# ESP_Bare_v2.net
KiCad netlist of a schematic drawn in EAGLE
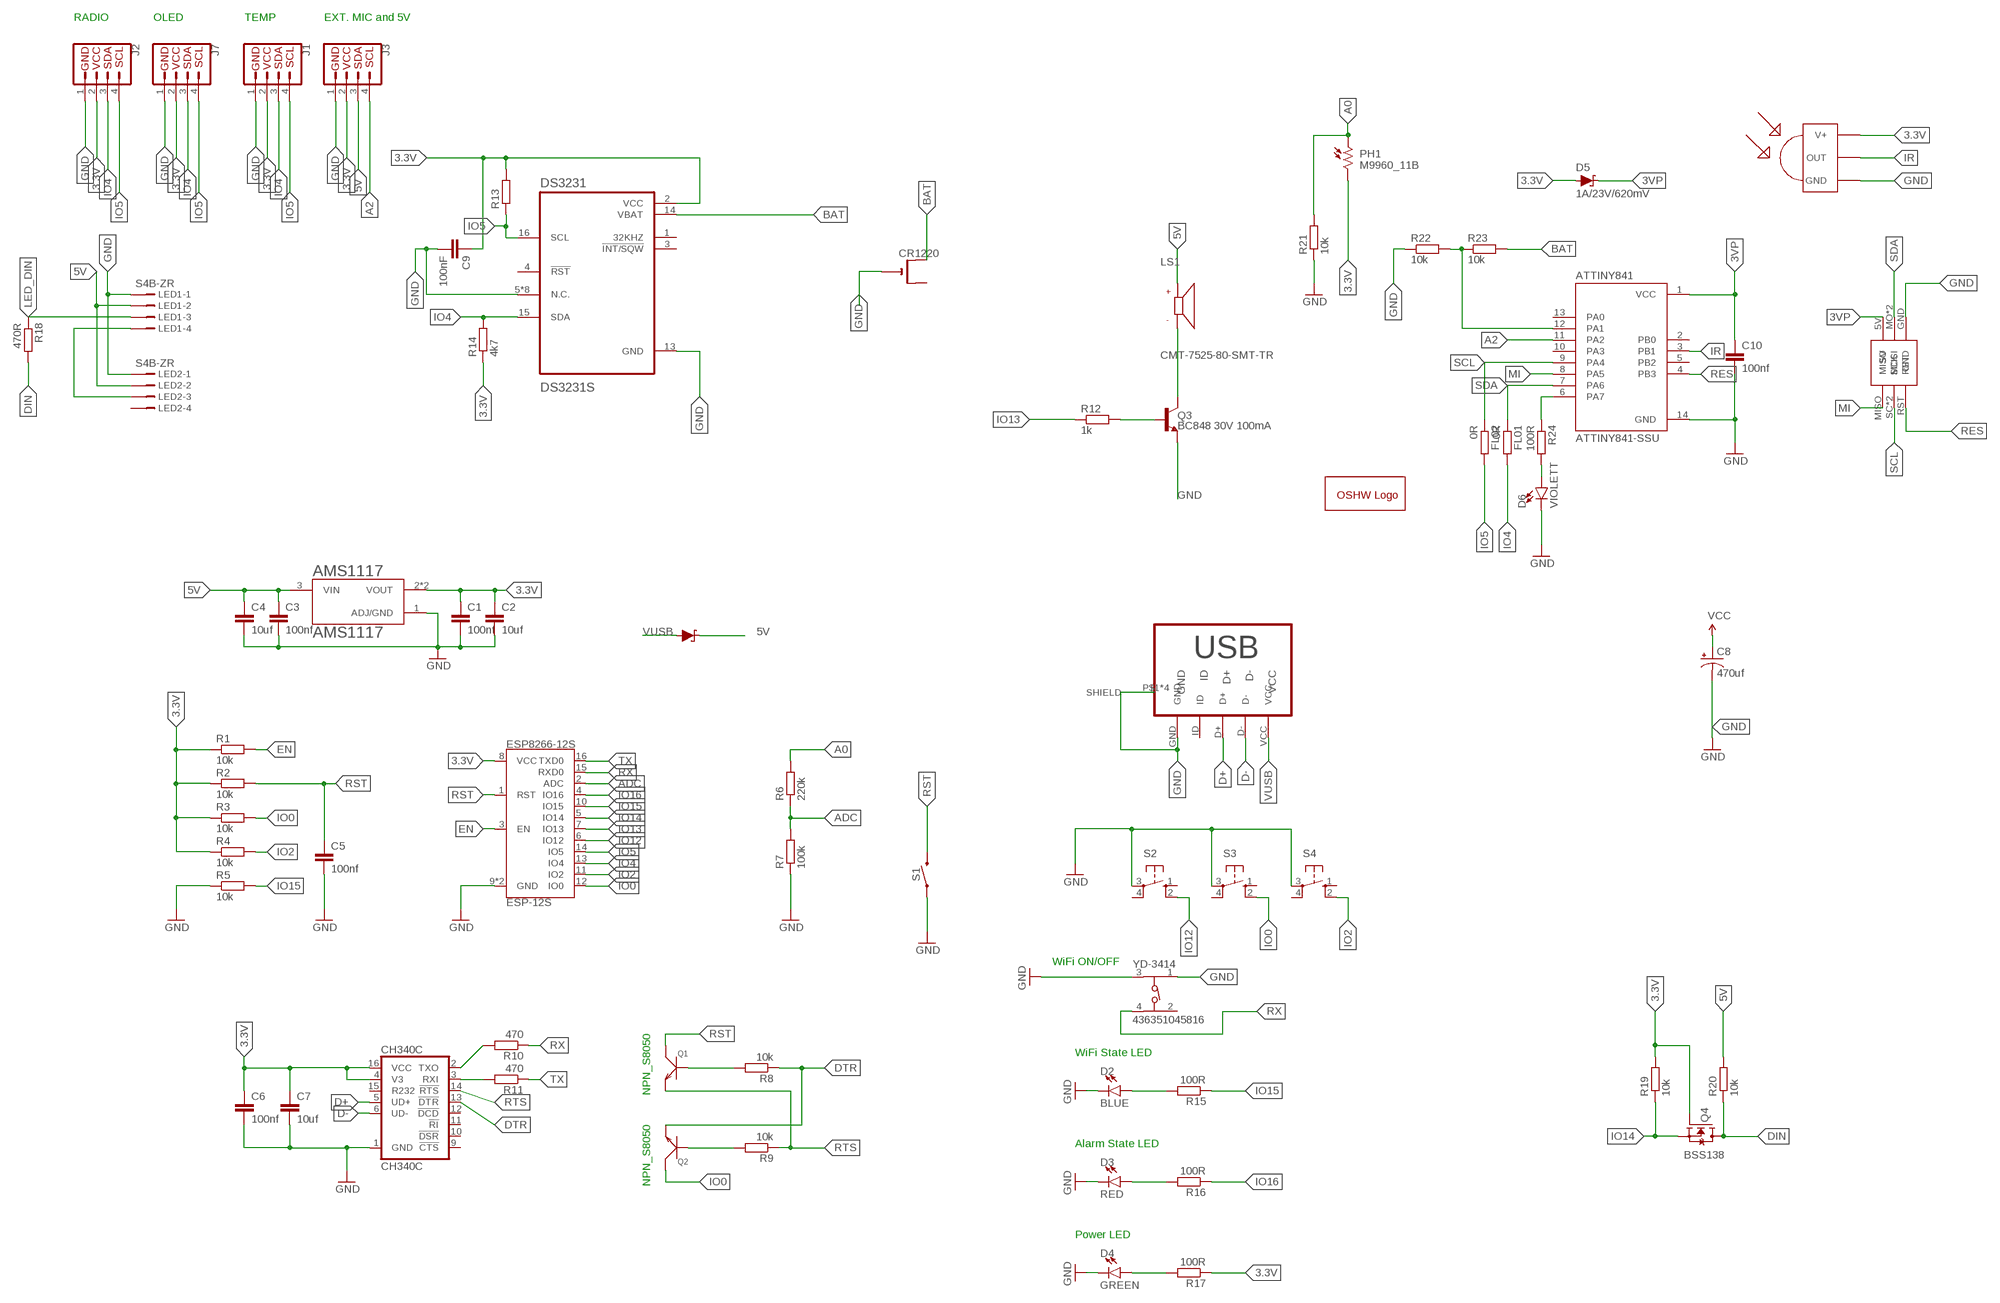
[diagram p0: schematic, sheet 1]

(export (version "E")
  (design (tool "Eeschema 10.0.6"))
  (components
    (comp (ref "AMS1117")
      (value "AMS1117")
      (footprint "eagle-import:SOT229P700X180-4N")
      (fields (field (name "MF") "Advanced Monolithic Systems"))
      (libsource (lib "eagle-import") (part "AMS1117"))
    )
    (comp (ref "ATTINY841")
      (value "ATTINY841-SSU")
      (footprint "eagle-import:SOIC127P599X175-14N")
      (fields (field (name "MF") "Microchip"))
      (libsource (lib "eagle-import") (part "ATTINY841-SSU"))
    )
    (comp (ref "C1")
      (value "100nf")
      (footprint "eagle-import:C0603")
      (libsource (lib "eagle-import") (part "C-EUC0603"))
    )
    (comp (ref "C2")
      (value "10uf")
      (footprint "eagle-import:C0805")
      (libsource (lib "eagle-import") (part "C-EUC0805"))
    )
    (comp (ref "C3")
      (value "100nf")
      (footprint "eagle-import:C0603")
      (libsource (lib "eagle-import") (part "C-EUC0603"))
    )
    (comp (ref "C4")
      (value "10uf")
      (footprint "eagle-import:C0805")
      (libsource (lib "eagle-import") (part "C-EUC0805"))
    )
    (comp (ref "C5")
      (value "100nf")
      (footprint "eagle-import:C0603")
      (libsource (lib "eagle-import") (part "C-EUC0603"))
    )
    (comp (ref "C6")
      (value "100nf")
      (footprint "eagle-import:C0603")
      (libsource (lib "eagle-import") (part "C-EUC0603"))
    )
    (comp (ref "C7")
      (value "10uf")
      (footprint "eagle-import:C0603")
      (libsource (lib "eagle-import") (part "C-EUC0603"))
    )
    (comp (ref "C8")
      (value "470uf")
      (footprint "eagle-import:EIA7343")
      (libsource (lib "eagle-import") (part "CAP_POL7343"))
    )
    (comp (ref "C9")
      (value "100nF")
      (footprint "eagle-import:C0603")
      (libsource (lib "eagle-import") (part "C-EUC0603"))
    )
    (comp (ref "C10")
      (value "100nf")
      (footprint "eagle-import:C0603")
      (libsource (lib "eagle-import") (part "C-EUC0603"))
    )
    (comp (ref "CH340C")
      (value "CH340C")
      (footprint "eagle-import:SO016")
      (fields (field (name "MF") "WCH"))
      (libsource (lib "eagle-import") (part "CH340C"))
    )
    (comp (ref "CR1220")
      (value "CR1220SMT")
      (footprint "eagle-import:CR1220-SMD")
      (libsource (lib "eagle-import") (part "CR1220SMT"))
    )
    (comp (ref "D1")
      (value "MBR130T1G, SL; SOD123 or SMA, 1A")
      (footprint "eagle-import:SMA-DIODE")
      (libsource (lib "eagle-import") (part "DIODE-SCHOTTKY-B340A"))
    )
    (comp (ref "D2")
      (value "BLUE")
      (footprint "eagle-import:LED-0603")
      (libsource (lib "eagle-import") (part "LED-BLUE0603"))
    )
    (comp (ref "D3")
      (value "RED")
      (footprint "eagle-import:LED-0603")
      (libsource (lib "eagle-import") (part "LED-BLUE0603"))
    )
    (comp (ref "D4")
      (value "GREEN")
      (footprint "eagle-import:LED-0603")
      (libsource (lib "eagle-import") (part "LED-BLUE0603"))
    )
    (comp (ref "D5")
      (value "1A/23V/620mV")
      (footprint "eagle-import:SOD-323")
      (libsource (lib "eagle-import") (part "DIODE-SCHOTTKY-BAT20J"))
    )
    (comp (ref "D6")
      (value "VIOLETT")
      (footprint "eagle-import:LED-0603")
      (libsource (lib "eagle-import") (part "LED-BLUE0603"))
    )
    (comp (ref "DS3231")
      (value "DS3231S")
      (footprint "eagle-import:SOIC127P1032X265-16N")
      (fields (field (name "MF") "Maxim Integrated"))
      (libsource (lib "eagle-import") (part "DS3231S"))
    )
    (comp (ref "ESP8266-12S")
      (value "ESP-12S")
      (footprint "eagle-import:ESP-12S")
      (fields (field (name "MF") "RF Solutions"))
      (libsource (lib "eagle-import") (part "ESP-12S"))
    )
    (comp (ref "FL01")
      (value "0R")
      (footprint "eagle-import:R0603")
      (libsource (lib "eagle-import") (part "R-EU_R0603"))
    )
    (comp (ref "FL02")
      (value "0R")
      (footprint "eagle-import:R0603")
      (libsource (lib "eagle-import") (part "R-EU_R0603"))
    )
    (comp (ref "GOLD_ORB_SM1")
      (value "OSHWLOGOLOGO5MM")
      (footprint "eagle-import:OSHW_5MM")
      (libsource (lib "eagle-import") (part "OSHWLOGOLOGO5MM"))
    )
    (comp (ref "J1")
      (value "QWIIC_CONNECTORJS-1MM")
      (footprint "eagle-import:1X04_1MM_RA")
      (libsource (lib "eagle-import") (part "QWIIC_CONNECTORJS-1MM"))
    )
    (comp (ref "J2")
      (value "QWIIC_CONNECTORJS-1MM")
      (footprint "eagle-import:1X04_1MM_RA")
      (libsource (lib "eagle-import") (part "QWIIC_CONNECTORJS-1MM"))
    )
    (comp (ref "J3")
      (value "QWIIC_CONNECTORJS-1MM")
      (footprint "eagle-import:1X04_1MM_RA")
      (libsource (lib "eagle-import") (part "QWIIC_CONNECTORJS-1MM"))
    )
    (comp (ref "J7")
      (value "QWIIC_CONNECTORJS-1MM")
      (footprint "eagle-import:1X04_1MM_RA")
      (libsource (lib "eagle-import") (part "QWIIC_CONNECTORJS-1MM"))
    )
    (comp (ref "LED1")
      (value "S4B-ZR")
      (footprint "eagle-import:S4B-ZR")
      (fields (field (name "MF") "FARNELL") (field (name "MPN") "S4B-ZR(LF)(SN)"))
      (libsource (lib "eagle-import") (part "?4B-ZRS"))
    )
    (comp (ref "LED2")
      (value "S4B-ZR")
      (footprint "eagle-import:S4B-ZR")
      (fields (field (name "MF") "FARNELL") (field (name "MPN") "S4B-ZR(LF)(SN)"))
      (libsource (lib "eagle-import") (part "?4B-ZRS"))
    )
    (comp (ref "LS1")
      (value "CMT-7525-80-SMT-TR")
      (footprint "eagle-import:XDCR_CMT-7525-80-SMT-TR")
      (fields (field (name "MF") "CUI Devices"))
      (libsource (lib "eagle-import") (part "CMT-7525-80-SMT-TR"))
    )
    (comp (ref "MICRO-USB")
      (value "MICRO-USB-B")
      (footprint "eagle-import:MICRO_USB_4_LEGS")
      (libsource (lib "eagle-import") (part "MICRO-USB-B"))
    )
    (comp (ref "PH1")
      (value "M9960_11B")
      (footprint "eagle-import:M9960")
      (libsource (lib "eagle-import") (part "M9960_11B"))
    )
    (comp (ref "Q1")
      (value "NPN_S8050")
      (footprint "eagle-import:SOT-23")
      (fields (field (name "MF") "Microdiode Electronics") (field (name "MP") "S8050"))
      (libsource (lib "eagle-import") (part "SMD-TRANSISTORS-NPN-25V-500MW(SOT-23)"))
    )
    (comp (ref "Q2")
      (value "NPN_S8050")
      (footprint "eagle-import:SOT-23")
      (fields (field (name "MF") "Microdiode Electronics") (field (name "MP") "S8050"))
      (libsource (lib "eagle-import") (part "SMD-TRANSISTORS-NPN-25V-500MW(SOT-23)"))
    )
    (comp (ref "Q3")
      (value "BC848 30V 100mA")
      (footprint "eagle-import:SOT23-3")
      (libsource (lib "eagle-import") (part "TRANS_NPN-MMBT2222AL"))
    )
    (comp (ref "Q4")
      (value "BSS138")
      (footprint "eagle-import:SOT95P240X111-3N")
      (fields (field (name "MF") "ON Semiconductor"))
      (libsource (lib "eagle-import") (part "BSS138"))
    )
    (comp (ref "R1")
      (value "10k")
      (footprint "eagle-import:R0603")
      (libsource (lib "eagle-import") (part "resistor_348_R-EU_R0603"))
    )
    (comp (ref "R2")
      (value "10k")
      (footprint "eagle-import:R0603")
      (libsource (lib "eagle-import") (part "resistor_348_R-EU_R0603"))
    )
    (comp (ref "R3")
      (value "10k")
      (footprint "eagle-import:R0603")
      (libsource (lib "eagle-import") (part "resistor_348_R-EU_R0603"))
    )
    (comp (ref "R4")
      (value "10k")
      (footprint "eagle-import:R0603")
      (libsource (lib "eagle-import") (part "resistor_348_R-EU_R0603"))
    )
    (comp (ref "R5")
      (value "10k")
      (footprint "eagle-import:R0603")
      (libsource (lib "eagle-import") (part "resistor_348_R-EU_R0603"))
    )
    (comp (ref "R6")
      (value "220k")
      (footprint "eagle-import:R0603")
      (libsource (lib "eagle-import") (part "resistor_348_R-EU_R0603"))
    )
    (comp (ref "R7")
      (value "100k")
      (footprint "eagle-import:R0603")
      (libsource (lib "eagle-import") (part "resistor_348_R-EU_R0603"))
    )
    (comp (ref "R8")
      (value "10k")
      (footprint "eagle-import:R0603")
      (libsource (lib "eagle-import") (part "resistor_348_R-EU_R0603"))
    )
    (comp (ref "R9")
      (value "10k")
      (footprint "eagle-import:R0603")
      (libsource (lib "eagle-import") (part "resistor_348_R-EU_R0603"))
    )
    (comp (ref "R10")
      (value "470")
      (footprint "eagle-import:R0603")
      (libsource (lib "eagle-import") (part "resistor_348_R-EU_R0603"))
    )
    (comp (ref "R11")
      (value "470")
      (footprint "eagle-import:R0603")
      (libsource (lib "eagle-import") (part "resistor_348_R-EU_R0603"))
    )
    (comp (ref "R12")
      (value "1k")
      (footprint "eagle-import:R0603")
      (libsource (lib "eagle-import") (part "R-EU_R0603"))
    )
    (comp (ref "R13")
      (value "4k7")
      (footprint "eagle-import:R0603")
      (libsource (lib "eagle-import") (part "resistor_348_R-EU_R0603"))
    )
    (comp (ref "R14")
      (value "4k7")
      (footprint "eagle-import:R0603")
      (libsource (lib "eagle-import") (part "resistor_348_R-EU_R0603"))
    )
    (comp (ref "R15")
      (value "100R")
      (footprint "eagle-import:R0603")
      (libsource (lib "eagle-import") (part "resistor_348_R-EU_R0603"))
    )
    (comp (ref "R16")
      (value "100R")
      (footprint "eagle-import:R0603")
      (libsource (lib "eagle-import") (part "resistor_348_R-EU_R0603"))
    )
    (comp (ref "R17")
      (value "100R")
      (footprint "eagle-import:R0603")
      (libsource (lib "eagle-import") (part "resistor_348_R-EU_R0603"))
    )
    (comp (ref "R18")
      (value "470R")
      (footprint "eagle-import:R0603")
      (libsource (lib "eagle-import") (part "resistor_348_R-EU_R0603"))
    )
    (comp (ref "R19")
      (value "10k")
      (footprint "eagle-import:R0603")
      (libsource (lib "eagle-import") (part "resistor_348_R-EU_R0603"))
    )
    (comp (ref "R20")
      (value "10k")
      (footprint "eagle-import:R0603")
      (libsource (lib "eagle-import") (part "resistor_348_R-EU_R0603"))
    )
    (comp (ref "R21")
      (value "10k")
      (footprint "eagle-import:R0603")
      (libsource (lib "eagle-import") (part "R-EU_R0603"))
    )
    (comp (ref "R22")
      (value "10k")
      (footprint "eagle-import:R0603")
      (libsource (lib "eagle-import") (part "R-EU_R0603"))
    )
    (comp (ref "R23")
      (value "10k")
      (footprint "eagle-import:R0603")
      (libsource (lib "eagle-import") (part "R-EU_R0603"))
    )
    (comp (ref "R24")
      (value "100R")
      (footprint "eagle-import:R0603")
      (libsource (lib "eagle-import") (part "R-EU_R0603"))
    )
    (comp (ref "S1")
      (value "MOMENTARY-SWITCH-SPST-SMD-4.6X2.8MM")
      (footprint "eagle-import:TACTILE_SWITCH_SMD_4.6X2.8MM")
      (libsource (lib "eagle-import") (part "MOMENTARY-SWITCH-SPST-SMD-4.6X2.8MM"))
    )
    (comp (ref "S2")
      (value "10-XX")
      (footprint "eagle-import:B3F-10XX")
      (fields (field (name "MPN") "B3F-1000"))
      (libsource (lib "eagle-import") (part "10-XX"))
    )
    (comp (ref "S3")
      (value "10-XX")
      (footprint "eagle-import:B3F-10XX")
      (fields (field (name "MPN") "B3F-1000"))
      (libsource (lib "eagle-import") (part "10-XX"))
    )
    (comp (ref "S4")
      (value "10-XX")
      (footprint "eagle-import:B3F-10XX")
      (fields (field (name "MPN") "B3F-1000"))
      (libsource (lib "eagle-import") (part "10-XX"))
    )
    (comp (ref "U$1")
      (value "ISCP_PORTPOGONEW")
      (footprint "eagle-import:ISCP_PADS_2ROW2HNEW")
      (libsource (lib "eagle-import") (part "ISCP_PORTPOGONEW"))
    )
    (comp (ref "U$2")
      (value "TSOP4838")
      (footprint "eagle-import:TSOP18XX")
      (fields (field (name "MF") "Vishay"))
      (libsource (lib "eagle-import") (part "TSOP4838"))
    )
    (comp (ref "YD-3414")
      (value "436351045816")
      (footprint "eagle-import:4363X10458XX")
      (libsource (lib "eagle-import") (part "436351045816"))
    )
  )
  (nets
    (net (code "1") (name "3.3V") (class "Default")
      (node (ref "AMS1117") (pin "2") (pinfunction "VOUT_2") (pintype "output"))
      (node (ref "AMS1117") (pin "4") (pinfunction "VOUT_4") (pintype "output"))
      (node (ref "C1") (pin "1") (pinfunction "1_1") (pintype "passive"))
      (node (ref "C2") (pin "1") (pinfunction "1_1") (pintype "passive"))
      (node (ref "C6") (pin "1") (pinfunction "1_1") (pintype "passive"))
      (node (ref "C7") (pin "1") (pinfunction "1_1") (pintype "passive"))
      (node (ref "C9") (pin "1") (pinfunction "1_1") (pintype "passive"))
      (node (ref "CH340C") (pin "16") (pinfunction "VCC_16") (pintype "bidirectional"))
      (node (ref "CH340C") (pin "4") (pinfunction "V3_4") (pintype "bidirectional"))
      (node (ref "D5") (pin "A") (pinfunction "A_A") (pintype "passive"))
      (node (ref "DS3231") (pin "2") (pinfunction "VCC_2") (pintype "power_in"))
      (node (ref "ESP8266-12S") (pin "8") (pinfunction "VCC_8") (pintype "bidirectional"))
      (node (ref "J1") (pin "2") (pinfunction "VCC_2") (pintype "power_in"))
      (node (ref "J2") (pin "2") (pinfunction "VCC_2") (pintype "power_in"))
      (node (ref "J3") (pin "2") (pinfunction "VCC_2") (pintype "power_in"))
      (node (ref "J7") (pin "2") (pinfunction "VCC_2") (pintype "power_in"))
      (node (ref "PH1") (pin "2") (pinfunction "2_2") (pintype "passive"))
      (node (ref "Q4") (pin "1") (pinfunction "G_1") (pintype "passive"))
      (node (ref "R1") (pin "1") (pinfunction "1_1") (pintype "passive"))
      (node (ref "R13") (pin "2") (pinfunction "2_2") (pintype "passive"))
      (node (ref "R14") (pin "1") (pinfunction "1_1") (pintype "passive"))
      (node (ref "R17") (pin "1") (pinfunction "1_1") (pintype "passive"))
      (node (ref "R19") (pin "2") (pinfunction "2_2") (pintype "passive"))
      (node (ref "R2") (pin "1") (pinfunction "1_1") (pintype "passive"))
      (node (ref "R3") (pin "1") (pinfunction "1_1") (pintype "passive"))
      (node (ref "R4") (pin "1") (pinfunction "1_1") (pintype "passive"))
      (node (ref "U$2") (pin "VCC") (pinfunction "V+_VCC") (pintype "bidirectional"))
    )
    (net (code "2") (name "3VP") (class "Default")
      (node (ref "ATTINY841") (pin "1") (pinfunction "VCC_1") (pintype "power_in"))
      (node (ref "C10") (pin "1") (pinfunction "1_1") (pintype "passive"))
      (node (ref "D5") (pin "C") (pinfunction "C_C") (pintype "passive"))
      (node (ref "U$1") (pin "5V") (pinfunction "5V_5V") (pintype "bidirectional"))
    )
    (net (code "3") (name "5V") (class "Default")
      (node (ref "AMS1117") (pin "3") (pinfunction "VIN_3") (pintype "input"))
      (node (ref "C3") (pin "1") (pinfunction "1_1") (pintype "passive"))
      (node (ref "C4") (pin "1") (pinfunction "1_1") (pintype "passive"))
      (node (ref "C8") (pin "A") (pinfunction "+_A") (pintype "passive"))
      (node (ref "D1") (pin "C") (pinfunction "C_C") (pintype "passive"))
      (node (ref "J3") (pin "3") (pinfunction "SDA_3") (pintype "passive"))
      (node (ref "LED1") (pin "2") (pinfunction "1_2") (pintype "passive"))
      (node (ref "LED2") (pin "2") (pinfunction "1_2") (pintype "passive"))
      (node (ref "LS1") (pin "P") (pinfunction "P_P") (pintype "passive"))
      (node (ref "R20") (pin "2") (pinfunction "2_2") (pintype "passive"))
    )
    (net (code "4") (name "A0") (class "Default")
      (node (ref "PH1") (pin "1") (pinfunction "1_1") (pintype "passive"))
      (node (ref "R21") (pin "2") (pinfunction "2_2") (pintype "passive"))
      (node (ref "R6") (pin "2") (pinfunction "2_2") (pintype "passive"))
    )
    (net (code "5") (name "A2") (class "Default")
      (node (ref "ATTINY841") (pin "11") (pinfunction "PA2_11") (pintype "bidirectional"))
      (node (ref "J3") (pin "4") (pinfunction "SCL_4") (pintype "passive"))
    )
    (net (code "6") (name "ADC") (class "Default")
      (node (ref "ESP8266-12S") (pin "2") (pinfunction "ADC_2") (pintype "bidirectional"))
      (node (ref "R6") (pin "1") (pinfunction "1_1") (pintype "passive"))
      (node (ref "R7") (pin "2") (pinfunction "2_2") (pintype "passive"))
    )
    (net (code "7") (name "BAT") (class "Default")
      (node (ref "CR1220") (pin "+$1") (pinfunction "+_+$1") (pintype "passive"))
      (node (ref "DS3231") (pin "14") (pinfunction "VBAT_14") (pintype "power_in"))
      (node (ref "R23") (pin "2") (pinfunction "2_2") (pintype "passive"))
    )
    (net (code "8") (name "D+") (class "Default")
      (node (ref "CH340C") (pin "5") (pinfunction "UD+_5") (pintype "bidirectional"))
      (node (ref "MICRO-USB") (pin "D+") (pinfunction "D+_D+") (pintype "bidirectional"))
    )
    (net (code "9") (name "D-") (class "Default")
      (node (ref "CH340C") (pin "6") (pinfunction "UD-_6") (pintype "bidirectional"))
      (node (ref "MICRO-USB") (pin "D-") (pinfunction "D-_D-") (pintype "bidirectional"))
    )
    (net (code "10") (name "DIN") (class "Default")
      (node (ref "Q4") (pin "3") (pinfunction "D_3") (pintype "passive"))
      (node (ref "R18") (pin "2") (pinfunction "2_2") (pintype "passive"))
      (node (ref "R20") (pin "1") (pinfunction "1_1") (pintype "passive"))
    )
    (net (code "11") (name "DTR") (class "Default")
      (node (ref "CH340C") (pin "13") (pinfunction "~{DTR}_13") (pintype "bidirectional"))
      (node (ref "Q2") (pin "2") (pinfunction "E_2") (pintype "passive"))
      (node (ref "R8") (pin "1") (pinfunction "1_1") (pintype "passive"))
    )
    (net (code "12") (name "EN") (class "Default")
      (node (ref "ESP8266-12S") (pin "3") (pinfunction "EN_3") (pintype "bidirectional"))
      (node (ref "R1") (pin "2") (pinfunction "2_2") (pintype "passive"))
    )
    (net (code "13") (name "GND") (class "Default")
      (node (ref "AMS1117") (pin "1") (pinfunction "ADJ/GND_1") (pintype "power_in"))
      (node (ref "ATTINY841") (pin "14") (pinfunction "GND_14") (pintype "power_in"))
      (node (ref "C1") (pin "2") (pinfunction "2_2") (pintype "passive"))
      (node (ref "C10") (pin "2") (pinfunction "2_2") (pintype "passive"))
      (node (ref "C2") (pin "2") (pinfunction "2_2") (pintype "passive"))
      (node (ref "C3") (pin "2") (pinfunction "2_2") (pintype "passive"))
      (node (ref "C4") (pin "2") (pinfunction "2_2") (pintype "passive"))
      (node (ref "C5") (pin "2") (pinfunction "2_2") (pintype "passive"))
      (node (ref "C6") (pin "2") (pinfunction "2_2") (pintype "passive"))
      (node (ref "C7") (pin "2") (pinfunction "2_2") (pintype "passive"))
      (node (ref "C8") (pin "C") (pinfunction "-_C") (pintype "passive"))
      (node (ref "C9") (pin "2") (pinfunction "2_2") (pintype "passive"))
      (node (ref "CH340C") (pin "1") (pinfunction "GND_1") (pintype "bidirectional"))
      (node (ref "CR1220") (pin "-") (pinfunction "-_-") (pintype "passive"))
      (node (ref "D2") (pin "C") (pinfunction "C_C") (pintype "passive"))
      (node (ref "D3") (pin "C") (pinfunction "C_C") (pintype "passive"))
      (node (ref "D4") (pin "C") (pinfunction "C_C") (pintype "passive"))
      (node (ref "D6") (pin "C") (pinfunction "C_C") (pintype "passive"))
      (node (ref "DS3231") (pin "10") (pinfunction "N.C._10") (pintype "bidirectional"))
      (node (ref "DS3231") (pin "11") (pinfunction "N.C._11") (pintype "bidirectional"))
      (node (ref "DS3231") (pin "12") (pinfunction "N.C._12") (pintype "bidirectional"))
      (node (ref "DS3231") (pin "13") (pinfunction "GND_13") (pintype "power_in"))
      (node (ref "DS3231") (pin "5") (pinfunction "N.C._5") (pintype "bidirectional"))
      (node (ref "DS3231") (pin "6") (pinfunction "N.C._6") (pintype "bidirectional"))
      (node (ref "DS3231") (pin "7") (pinfunction "N.C._7") (pintype "bidirectional"))
      (node (ref "DS3231") (pin "8") (pinfunction "N.C._8") (pintype "bidirectional"))
      (node (ref "DS3231") (pin "9") (pinfunction "N.C._9") (pintype "bidirectional"))
      (node (ref "ESP8266-12S") (pin "9") (pinfunction "GND_9") (pintype "bidirectional"))
      (node (ref "ESP8266-12S") (pin "P$1") (pinfunction "GND_P$1") (pintype "bidirectional"))
      (node (ref "J1") (pin "1") (pinfunction "GND_1") (pintype "power_in"))
      (node (ref "J2") (pin "1") (pinfunction "GND_1") (pintype "power_in"))
      (node (ref "J3") (pin "1") (pinfunction "GND_1") (pintype "power_in"))
      (node (ref "J7") (pin "1") (pinfunction "GND_1") (pintype "power_in"))
      (node (ref "LED1") (pin "1") (pinfunction "1_1") (pintype "passive"))
      (node (ref "LED2") (pin "1") (pinfunction "1_1") (pintype "passive"))
      (node (ref "MICRO-USB") (pin "GND") (pinfunction "GND_GND") (pintype "bidirectional"))
      (node (ref "MICRO-USB") (pin "P$1") (pinfunction "SHIELD_P$1") (pintype "bidirectional"))
      (node (ref "MICRO-USB") (pin "P$2") (pinfunction "SHIELD_P$2") (pintype "bidirectional"))
      (node (ref "MICRO-USB") (pin "P$3") (pinfunction "SHIELD_P$3") (pintype "bidirectional"))
      (node (ref "MICRO-USB") (pin "P$5") (pinfunction "SHIELD_P$5") (pintype "bidirectional"))
      (node (ref "Q3") (pin "2") (pinfunction "E_2") (pintype "passive"))
      (node (ref "R21") (pin "1") (pinfunction "1_1") (pintype "passive"))
      (node (ref "R22") (pin "1") (pinfunction "1_1") (pintype "passive"))
      (node (ref "R5") (pin "1") (pinfunction "1_1") (pintype "passive"))
      (node (ref "R7") (pin "1") (pinfunction "1_1") (pintype "passive"))
      (node (ref "S1") (pin "1") (pinfunction "1_1") (pintype "passive"))
      (node (ref "S1") (pin "2") (pinfunction "1_2") (pintype "passive"))
      (node (ref "S2") (pin "3") (pinfunction "P_3") (pintype "passive"))
      (node (ref "S3") (pin "3") (pinfunction "P_3") (pintype "passive"))
      (node (ref "S4") (pin "3") (pinfunction "P_3") (pintype "passive"))
      (node (ref "U$1") (pin "GND") (pinfunction "GND_GND") (pintype "bidirectional"))
      (node (ref "U$2") (pin "GND") (pinfunction "GND_GND") (pintype "bidirectional"))
      (node (ref "YD-3414") (pin "1") (pinfunction "3_1") (pintype "passive"))
      (node (ref "YD-3414") (pin "3") (pinfunction "1_3") (pintype "passive"))
    )
    (net (code "14") (name "IO0") (class "Default")
      (node (ref "ESP8266-12S") (pin "12") (pinfunction "IO0_12") (pintype "bidirectional"))
      (node (ref "Q2") (pin "3") (pinfunction "C_3") (pintype "passive"))
      (node (ref "R3") (pin "2") (pinfunction "2_2") (pintype "passive"))
      (node (ref "S3") (pin "2") (pinfunction "S1_2") (pintype "passive"))
    )
    (net (code "15") (name "IO2") (class "Default")
      (node (ref "ESP8266-12S") (pin "11") (pinfunction "IO2_11") (pintype "bidirectional"))
      (node (ref "R4") (pin "2") (pinfunction "2_2") (pintype "passive"))
      (node (ref "S4") (pin "2") (pinfunction "S1_2") (pintype "passive"))
    )
    (net (code "16") (name "IO4") (class "Default")
      (node (ref "DS3231") (pin "15") (pinfunction "SDA_15") (pintype "bidirectional"))
      (node (ref "ESP8266-12S") (pin "13") (pinfunction "IO4_13") (pintype "bidirectional"))
      (node (ref "FL01") (pin "2") (pinfunction "2_2") (pintype "passive"))
      (node (ref "J1") (pin "3") (pinfunction "SDA_3") (pintype "passive"))
      (node (ref "J2") (pin "3") (pinfunction "SDA_3") (pintype "passive"))
      (node (ref "J7") (pin "3") (pinfunction "SDA_3") (pintype "passive"))
      (node (ref "R14") (pin "2") (pinfunction "2_2") (pintype "passive"))
    )
    (net (code "17") (name "IO5") (class "Default")
      (node (ref "DS3231") (pin "16") (pinfunction "SCL_16") (pintype "input"))
      (node (ref "ESP8266-12S") (pin "14") (pinfunction "IO5_14") (pintype "bidirectional"))
      (node (ref "FL02") (pin "2") (pinfunction "2_2") (pintype "passive"))
      (node (ref "J1") (pin "4") (pinfunction "SCL_4") (pintype "passive"))
      (node (ref "J2") (pin "4") (pinfunction "SCL_4") (pintype "passive"))
      (node (ref "J7") (pin "4") (pinfunction "SCL_4") (pintype "passive"))
      (node (ref "R13") (pin "1") (pinfunction "1_1") (pintype "passive"))
    )
    (net (code "18") (name "IO12") (class "Default")
      (node (ref "ESP8266-12S") (pin "6") (pinfunction "IO12_6") (pintype "bidirectional"))
      (node (ref "S2") (pin "2") (pinfunction "S1_2") (pintype "passive"))
    )
    (net (code "19") (name "IO13") (class "Default")
      (node (ref "ESP8266-12S") (pin "7") (pinfunction "IO13_7") (pintype "bidirectional"))
      (node (ref "R12") (pin "1") (pinfunction "1_1") (pintype "passive"))
    )
    (net (code "20") (name "IO14") (class "Default")
      (node (ref "ESP8266-12S") (pin "5") (pinfunction "IO14_5") (pintype "bidirectional"))
      (node (ref "Q4") (pin "2") (pinfunction "S_2") (pintype "passive"))
      (node (ref "R19") (pin "1") (pinfunction "1_1") (pintype "passive"))
    )
    (net (code "21") (name "IO15") (class "Default")
      (node (ref "ESP8266-12S") (pin "10") (pinfunction "IO15_10") (pintype "bidirectional"))
      (node (ref "R15") (pin "1") (pinfunction "1_1") (pintype "passive"))
      (node (ref "R5") (pin "2") (pinfunction "2_2") (pintype "passive"))
    )
    (net (code "22") (name "IO16") (class "Default")
      (node (ref "ESP8266-12S") (pin "4") (pinfunction "IO16_4") (pintype "bidirectional"))
      (node (ref "R16") (pin "1") (pinfunction "1_1") (pintype "passive"))
    )
    (net (code "23") (name "IR") (class "Default")
      (node (ref "ATTINY841") (pin "3") (pinfunction "PB1_3") (pintype "bidirectional"))
      (node (ref "U$2") (pin "OUT") (pinfunction "OUT_OUT") (pintype "bidirectional"))
    )
    (net (code "24") (name "LED_DIN") (class "Default")
      (node (ref "LED1") (pin "3") (pinfunction "1_3") (pintype "passive"))
      (node (ref "R18") (pin "1") (pinfunction "1_1") (pintype "passive"))
    )
    (net (code "25") (name "MI") (class "Default")
      (node (ref "ATTINY841") (pin "8") (pinfunction "PA5_8") (pintype "bidirectional"))
      (node (ref "U$1") (pin "MISO") (pinfunction "MISO_MISO") (pintype "bidirectional"))
    )
    (net (code "26") (name "Net-(ATTINY841-PA1)") (class "Default")
      (node (ref "ATTINY841") (pin "12") (pinfunction "PA1_12") (pintype "bidirectional"))
      (node (ref "R22") (pin "2") (pinfunction "2_2") (pintype "passive"))
      (node (ref "R23") (pin "1") (pinfunction "1_1") (pintype "passive"))
    )
    (net (code "27") (name "Net-(ATTINY841-PA7)") (class "Default")
      (node (ref "ATTINY841") (pin "6") (pinfunction "PA7_6") (pintype "bidirectional"))
      (node (ref "R24") (pin "1") (pinfunction "1_1") (pintype "passive"))
    )
    (net (code "28") (name "Net-(CH340C-RXI)") (class "Default")
      (node (ref "CH340C") (pin "3") (pinfunction "RXI_3") (pintype "bidirectional"))
      (node (ref "R11") (pin "2") (pinfunction "2_2") (pintype "passive"))
    )
    (net (code "29") (name "Net-(CH340C-TXO)") (class "Default")
      (node (ref "CH340C") (pin "2") (pinfunction "TXO_2") (pintype "bidirectional"))
      (node (ref "R10") (pin "2") (pinfunction "2_2") (pintype "passive"))
    )
    (net (code "30") (name "Net-(D2-PadA)") (class "Default")
      (node (ref "D2") (pin "A") (pinfunction "A_A") (pintype "passive"))
      (node (ref "R15") (pin "2") (pinfunction "2_2") (pintype "passive"))
    )
    (net (code "31") (name "Net-(D3-PadA)") (class "Default")
      (node (ref "D3") (pin "A") (pinfunction "A_A") (pintype "passive"))
      (node (ref "R16") (pin "2") (pinfunction "2_2") (pintype "passive"))
    )
    (net (code "32") (name "Net-(D4-PadA)") (class "Default")
      (node (ref "D4") (pin "A") (pinfunction "A_A") (pintype "passive"))
      (node (ref "R17") (pin "2") (pinfunction "2_2") (pintype "passive"))
    )
    (net (code "33") (name "Net-(D6-PadA)") (class "Default")
      (node (ref "D6") (pin "A") (pinfunction "A_A") (pintype "passive"))
      (node (ref "R24") (pin "2") (pinfunction "2_2") (pintype "passive"))
    )
    (net (code "34") (name "Net-(LED1D-1)") (class "Default")
      (node (ref "LED1") (pin "4") (pinfunction "1_4") (pintype "passive"))
      (node (ref "LED2") (pin "3") (pinfunction "1_3") (pintype "passive"))
    )
    (net (code "35") (name "Net-(Q1-B)") (class "Default")
      (node (ref "Q1") (pin "1") (pinfunction "B_1") (pintype "passive"))
      (node (ref "R8") (pin "2") (pinfunction "2_2") (pintype "passive"))
    )
    (net (code "36") (name "Net-(Q2-B)") (class "Default")
      (node (ref "Q2") (pin "1") (pinfunction "B_1") (pintype "passive"))
      (node (ref "R9") (pin "2") (pinfunction "2_2") (pintype "passive"))
    )
    (net (code "37") (name "Net-(Q3-B)") (class "Default")
      (node (ref "Q3") (pin "1") (pinfunction "B_1") (pintype "passive"))
      (node (ref "R12") (pin "2") (pinfunction "2_2") (pintype "passive"))
    )
    (net (code "38") (name "Net-(Q3-C)") (class "Default")
      (node (ref "LS1") (pin "N") (pinfunction "N_N") (pintype "passive"))
      (node (ref "Q3") (pin "3") (pinfunction "C_3") (pintype "passive"))
    )
    (net (code "39") (name "RES") (class "Default")
      (node (ref "ATTINY841") (pin "4") (pinfunction "PB3_4") (pintype "bidirectional"))
      (node (ref "U$1") (pin "RST") (pinfunction "RST_RST") (pintype "bidirectional"))
    )
    (net (code "40") (name "RST") (class "Default")
      (node (ref "C5") (pin "1") (pinfunction "1_1") (pintype "passive"))
      (node (ref "ESP8266-12S") (pin "1") (pinfunction "RST_1") (pintype "bidirectional"))
      (node (ref "Q1") (pin "3") (pinfunction "C_3") (pintype "passive"))
      (node (ref "R2") (pin "2") (pinfunction "2_2") (pintype "passive"))
      (node (ref "S1") (pin "3") (pinfunction "2_3") (pintype "passive"))
      (node (ref "S1") (pin "4") (pinfunction "2_4") (pintype "passive"))
    )
    (net (code "41") (name "RTS") (class "Default")
      (node (ref "CH340C") (pin "14") (pinfunction "~{RTS}_14") (pintype "bidirectional"))
      (node (ref "Q1") (pin "2") (pinfunction "E_2") (pintype "passive"))
      (node (ref "R9") (pin "1") (pinfunction "1_1") (pintype "passive"))
    )
    (net (code "42") (name "RX") (class "Default")
      (node (ref "ESP8266-12S") (pin "15") (pinfunction "RXD0_15") (pintype "bidirectional"))
      (node (ref "R10") (pin "1") (pinfunction "1_1") (pintype "passive"))
      (node (ref "YD-3414") (pin "4") (pinfunction "2_4") (pintype "passive"))
    )
    (net (code "43") (name "SCL") (class "Default")
      (node (ref "ATTINY841") (pin "9") (pinfunction "PA4_9") (pintype "bidirectional"))
      (node (ref "FL02") (pin "1") (pinfunction "1_1") (pintype "passive"))
      (node (ref "U$1") (pin "SC") (pinfunction "SCK_SC") (pintype "bidirectional"))
      (node (ref "U$1") (pin "SCK") (pinfunction "SCK_SCK") (pintype "bidirectional"))
    )
    (net (code "44") (name "SDA") (class "Default")
      (node (ref "ATTINY841") (pin "7") (pinfunction "PA6_7") (pintype "bidirectional"))
      (node (ref "FL01") (pin "1") (pinfunction "1_1") (pintype "passive"))
      (node (ref "U$1") (pin "MO") (pinfunction "MOSI_MO") (pintype "bidirectional"))
      (node (ref "U$1") (pin "MOSI") (pinfunction "MOSI_MOSI") (pintype "bidirectional"))
    )
    (net (code "45") (name "TX") (class "Default")
      (node (ref "ESP8266-12S") (pin "16") (pinfunction "TXD0_16") (pintype "bidirectional"))
      (node (ref "R11") (pin "1") (pinfunction "1_1") (pintype "passive"))
    )
    (net (code "46") (name "VUSB") (class "Default")
      (node (ref "D1") (pin "A") (pinfunction "A_A") (pintype "passive"))
      (node (ref "MICRO-USB") (pin "VCC") (pinfunction "VCC_VCC") (pintype "bidirectional"))
    )
    (net (code "47") (name "unconnected-(ATTINY841-PA0-Pad13)") (class "Default")
      (node (ref "ATTINY841") (pin "13") (pinfunction "PA0_13") (pintype "bidirectional"))
    )
    (net (code "48") (name "unconnected-(ATTINY841-PA3-Pad10)") (class "Default")
      (node (ref "ATTINY841") (pin "10") (pinfunction "PA3_10") (pintype "bidirectional"))
    )
    (net (code "49") (name "unconnected-(ATTINY841-PB0-Pad2)") (class "Default")
      (node (ref "ATTINY841") (pin "2") (pinfunction "PB0_2") (pintype "bidirectional"))
    )
    (net (code "50") (name "unconnected-(ATTINY841-PB2-Pad5)") (class "Default")
      (node (ref "ATTINY841") (pin "5") (pinfunction "PB2_5") (pintype "bidirectional"))
    )
    (net (code "51") (name "unconnected-(CH340C-R232-Pad15)") (class "Default")
      (node (ref "CH340C") (pin "15") (pinfunction "R232_15") (pintype "bidirectional"))
    )
    (net (code "52") (name "unconnected-(CH340C-~{CTS}-Pad9)") (class "Default")
      (node (ref "CH340C") (pin "9") (pinfunction "~{CTS}_9") (pintype "bidirectional"))
    )
    (net (code "53") (name "unconnected-(CH340C-~{DCD}-Pad12)") (class "Default")
      (node (ref "CH340C") (pin "12") (pinfunction "~{DCD}_12") (pintype "bidirectional"))
    )
    (net (code "54") (name "unconnected-(CH340C-~{DSR}-Pad10)") (class "Default")
      (node (ref "CH340C") (pin "10") (pinfunction "~{DSR}_10") (pintype "bidirectional"))
    )
    (net (code "55") (name "unconnected-(CH340C-~{RI}-Pad11)") (class "Default")
      (node (ref "CH340C") (pin "11") (pinfunction "~{RI}_11") (pintype "bidirectional"))
    )
    (net (code "56") (name "unconnected-(CR1220-+1-Pad+$2)") (class "Default")
      (node (ref "CR1220") (pin "+$2") (pinfunction "+1_+$2") (pintype "passive"))
    )
    (net (code "57") (name "unconnected-(DS3231-32KHZ-Pad1)") (class "Default")
      (node (ref "DS3231") (pin "1") (pinfunction "32KHZ_1") (pintype "output"))
    )
    (net (code "58") (name "unconnected-(DS3231-~{INT{slash}SQW}-Pad3)") (class "Default")
      (node (ref "DS3231") (pin "3") (pinfunction "~{INT/SQW}_3") (pintype "output"))
    )
    (net (code "59") (name "unconnected-(DS3231-~{RST}-Pad4)") (class "Default")
      (node (ref "DS3231") (pin "4") (pinfunction "~{RST}_4") (pintype "bidirectional"))
    )
    (net (code "60") (name "unconnected-(LED2D-1-Pad4)") (class "Default")
      (node (ref "LED2") (pin "4") (pinfunction "1_4") (pintype "passive"))
    )
    (net (code "61") (name "unconnected-(MICRO-USB-PadID)") (class "Default")
      (node (ref "MICRO-USB") (pin "ID") (pinfunction "ID_ID") (pintype "bidirectional"))
    )
    (net (code "62") (name "unconnected-(S2-P1-Pad4)") (class "Default")
      (node (ref "S2") (pin "4") (pinfunction "P1_4") (pintype "passive"))
    )
    (net (code "63") (name "unconnected-(S2-S-Pad1)") (class "Default")
      (node (ref "S2") (pin "1") (pinfunction "S_1") (pintype "passive"))
    )
    (net (code "64") (name "unconnected-(S3-P1-Pad4)") (class "Default")
      (node (ref "S3") (pin "4") (pinfunction "P1_4") (pintype "passive"))
    )
    (net (code "65") (name "unconnected-(S3-S-Pad1)") (class "Default")
      (node (ref "S3") (pin "1") (pinfunction "S_1") (pintype "passive"))
    )
    (net (code "66") (name "unconnected-(S4-P1-Pad4)") (class "Default")
      (node (ref "S4") (pin "4") (pinfunction "P1_4") (pintype "passive"))
    )
    (net (code "67") (name "unconnected-(S4-S-Pad1)") (class "Default")
      (node (ref "S4") (pin "1") (pinfunction "S_1") (pintype "passive"))
    )
    (net (code "68") (name "unconnected-(YD-3414-4-Pad2)") (class "Default")
      (node (ref "YD-3414") (pin "2") (pinfunction "4_2") (pintype "passive"))
    )
  )
)
